# manuellsteuerung.net
KiCad netlist of a schematic drawn in EAGLE
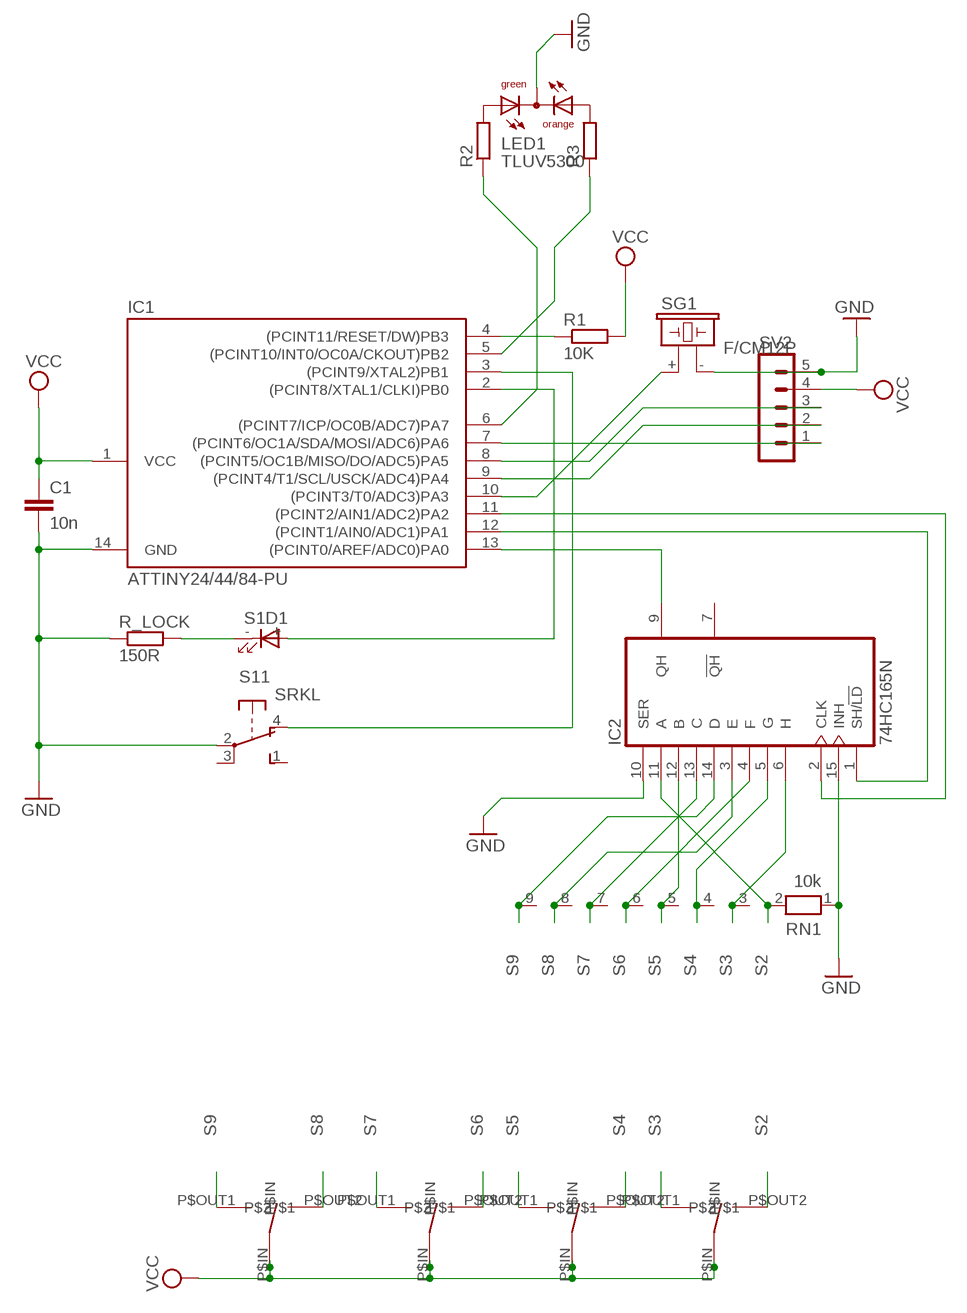
[diagram p0: schematic, sheet 1]

(export (version "E")
  (design (tool "Eeschema 10.0.6"))
  (components
    (comp (ref "C1")
      (value "10n")
      (footprint "eagle-import:C025-024X044")
      (libsource (lib "eagle-import") (part "C-EU025-024X044"))
    )
    (comp (ref "IC1")
      (value "ATTINY24/44/84-PU")
      (footprint "eagle-import:DIL14")
      (libsource (lib "eagle-import") (part "ATTINY24/44/84-PU"))
    )
    (comp (ref "IC2")
      (value "74HC165N")
      (footprint "eagle-import:DIL16")
      (libsource (lib "eagle-import") (part "74165NHC"))
    )
    (comp (ref "LED1")
      (value "TLUV5300")
      (footprint "eagle-import:TLUV5300")
      (libsource (lib "eagle-import") (part "TLUV5300"))
    )
    (comp (ref "R1")
      (value "10K")
      (footprint "eagle-import:0207_7")
      (libsource (lib "eagle-import") (part "R-EU_0207/7"))
    )
    (comp (ref "R2")
      (value "R-EU_0207/7")
      (footprint "eagle-import:0207_7")
      (libsource (lib "eagle-import") (part "R-EU_0207/7"))
    )
    (comp (ref "R3")
      (value "R-EU_0207/7")
      (footprint "eagle-import:0207_7")
      (libsource (lib "eagle-import") (part "R-EU_0207/7"))
    )
    (comp (ref "RN1")
      (value "10k")
      (footprint "eagle-import:RN-9")
      (libsource (lib "eagle-import") (part "RN08"))
    )
    (comp (ref "R_LOCK")
      (value "150R")
      (footprint "eagle-import:0207_10")
      (libsource (lib "eagle-import") (part "R-EU_0207/10"))
    )
    (comp (ref "S1")
      (value "SRKL")
      (footprint "eagle-import:SRKL")
      (libsource (lib "eagle-import") (part "SRKL"))
    )
    (comp (ref "SG1")
      (value "F/CM12P")
      (footprint "eagle-import:F_CM12P")
      (libsource (lib "eagle-import") (part "F/CM12P"))
    )
    (comp (ref "SV2")
      (value "MA05-1")
      (footprint "eagle-import:MA05-1")
      (libsource (lib "eagle-import") (part "MA05-1"))
    )
    (comp (ref "U$1")
      (value "MS_500E")
      (footprint "eagle-import:MS_500E")
      (libsource (lib "eagle-import") (part "MS_500E"))
    )
    (comp (ref "U$2")
      (value "MS_500E")
      (footprint "eagle-import:MS_500E")
      (libsource (lib "eagle-import") (part "MS_500E"))
    )
    (comp (ref "U$3")
      (value "MS_500E")
      (footprint "eagle-import:MS_500E")
      (libsource (lib "eagle-import") (part "MS_500E"))
    )
    (comp (ref "U$4")
      (value "MS_500E")
      (footprint "eagle-import:MS_500E")
      (libsource (lib "eagle-import") (part "MS_500E"))
    )
  )
  (nets
    (net (code "1") (name "/S2") (class "Default")
      (node (ref "IC2") (pin "11") (pinfunction "A_11") (pintype "input"))
      (node (ref "RN1") (pin "2") (pinfunction "2_2") (pintype "passive"))
      (node (ref "U$4") (pin "P$OUT2") (pinfunction "P$2_P$OUT2") (pintype "bidirectional"))
    )
    (net (code "2") (name "/S3") (class "Default")
      (node (ref "IC2") (pin "6") (pinfunction "H_6") (pintype "input"))
      (node (ref "RN1") (pin "3") (pinfunction "3_3") (pintype "passive"))
      (node (ref "U$4") (pin "P$OUT1") (pinfunction "P$1_P$OUT1") (pintype "bidirectional"))
    )
    (net (code "3") (name "/S4") (class "Default")
      (node (ref "IC2") (pin "5") (pinfunction "G_5") (pintype "input"))
      (node (ref "RN1") (pin "4") (pinfunction "4_4") (pintype "passive"))
      (node (ref "U$1") (pin "P$OUT2") (pinfunction "P$2_P$OUT2") (pintype "bidirectional"))
    )
    (net (code "4") (name "/S5") (class "Default")
      (node (ref "IC2") (pin "12") (pinfunction "B_12") (pintype "input"))
      (node (ref "RN1") (pin "5") (pinfunction "5_5") (pintype "passive"))
      (node (ref "U$1") (pin "P$OUT1") (pinfunction "P$1_P$OUT1") (pintype "bidirectional"))
    )
    (net (code "5") (name "/S6") (class "Default")
      (node (ref "IC2") (pin "4") (pinfunction "F_4") (pintype "input"))
      (node (ref "RN1") (pin "6") (pinfunction "6_6") (pintype "passive"))
      (node (ref "U$3") (pin "P$OUT2") (pinfunction "P$2_P$OUT2") (pintype "bidirectional"))
    )
    (net (code "6") (name "/S7") (class "Default")
      (node (ref "IC2") (pin "13") (pinfunction "C_13") (pintype "input"))
      (node (ref "RN1") (pin "7") (pinfunction "7_7") (pintype "passive"))
      (node (ref "U$3") (pin "P$OUT1") (pinfunction "P$1_P$OUT1") (pintype "bidirectional"))
    )
    (net (code "7") (name "/S8") (class "Default")
      (node (ref "IC2") (pin "3") (pinfunction "E_3") (pintype "input"))
      (node (ref "RN1") (pin "8") (pinfunction "8_8") (pintype "passive"))
      (node (ref "U$2") (pin "P$OUT2") (pinfunction "P$2_P$OUT2") (pintype "bidirectional"))
    )
    (net (code "8") (name "/S9") (class "Default")
      (node (ref "IC2") (pin "14") (pinfunction "D_14") (pintype "input"))
      (node (ref "RN1") (pin "9") (pinfunction "9_9") (pintype "passive"))
      (node (ref "U$2") (pin "P$OUT1") (pinfunction "P$1_P$OUT1") (pintype "bidirectional"))
    )
    (net (code "9") (name "GND") (class "Default")
      (node (ref "C1") (pin "2") (pinfunction "2_2") (pintype "passive"))
      (node (ref "IC1") (pin "14") (pinfunction "GND_14") (pintype "power_in"))
      (node (ref "IC2") (pin "10") (pinfunction "SER_10") (pintype "input"))
      (node (ref "IC2") (pin "15") (pinfunction "INH_15") (pintype "input"))
      (node (ref "LED1") (pin "CC") (pinfunction "CC_CC") (pintype "passive"))
      (node (ref "RN1") (pin "1") (pinfunction "1_1") (pintype "passive"))
      (node (ref "R_LOCK") (pin "1") (pinfunction "1_1") (pintype "passive"))
      (node (ref "S1") (pin "2") (pinfunction "P_2") (pintype "passive"))
      (node (ref "SG1") (pin "-") (pinfunction "2_-") (pintype "passive"))
      (node (ref "SV2") (pin "5") (pinfunction "5_5") (pintype "passive"))
    )
    (net (code "10") (name "Net-(IC1-(PCINT0{slash}AREF{slash}ADC0)PA0)") (class "Default")
      (node (ref "IC1") (pin "13") (pinfunction "(PCINT0/AREF/ADC0)PA0_13") (pintype "bidirectional"))
      (node (ref "IC2") (pin "9") (pinfunction "QH_9") (pintype "output"))
    )
    (net (code "11") (name "Net-(IC1-(PCINT1{slash}AIN0{slash}ADC1)PA1)") (class "Default")
      (node (ref "IC1") (pin "12") (pinfunction "(PCINT1/AIN0/ADC1)PA1_12") (pintype "bidirectional"))
      (node (ref "IC2") (pin "1") (pinfunction "SH/~{LD}_1") (pintype "input"))
    )
    (net (code "12") (name "Net-(IC1-(PCINT2{slash}AIN1{slash}ADC2)PA2)") (class "Default")
      (node (ref "IC1") (pin "11") (pinfunction "(PCINT2/AIN1/ADC2)PA2_11") (pintype "bidirectional"))
      (node (ref "IC2") (pin "2") (pinfunction "CLK_2") (pintype "input"))
    )
    (net (code "13") (name "Net-(IC1-(PCINT3{slash}T0{slash}ADC3)PA3)") (class "Default")
      (node (ref "IC1") (pin "10") (pinfunction "(PCINT3/T0/ADC3)PA3_10") (pintype "bidirectional"))
      (node (ref "SG1") (pin "+") (pinfunction "1_+") (pintype "passive"))
    )
    (net (code "14") (name "Net-(IC1-(PCINT4{slash}T1{slash}SCL{slash}USCK{slash}ADC4)PA4)") (class "Default")
      (node (ref "IC1") (pin "9") (pinfunction "(PCINT4/T1/SCL/USCK/ADC4)PA4_9") (pintype "bidirectional"))
      (node (ref "SV2") (pin "2") (pinfunction "2_2") (pintype "passive"))
    )
    (net (code "15") (name "Net-(IC1-(PCINT5{slash}OC1B{slash}MISO{slash}DO{slash}ADC5)PA5)") (class "Default")
      (node (ref "IC1") (pin "8") (pinfunction "(PCINT5/OC1B/MISO/DO/ADC5)PA5_8") (pintype "bidirectional"))
      (node (ref "SV2") (pin "3") (pinfunction "3_3") (pintype "passive"))
    )
    (net (code "16") (name "Net-(IC1-(PCINT6{slash}OC1A{slash}SDA{slash}MOSI{slash}ADC6)PA6)") (class "Default")
      (node (ref "IC1") (pin "7") (pinfunction "(PCINT6/OC1A/SDA/MOSI/ADC6)PA6_7") (pintype "bidirectional"))
      (node (ref "SV2") (pin "1") (pinfunction "1_1") (pintype "passive"))
    )
    (net (code "17") (name "Net-(IC1-(PCINT7{slash}ICP{slash}OC0B{slash}ADC7)PA7)") (class "Default")
      (node (ref "IC1") (pin "6") (pinfunction "(PCINT7/ICP/OC0B/ADC7)PA7_6") (pintype "bidirectional"))
      (node (ref "R2") (pin "1") (pinfunction "1_1") (pintype "passive"))
    )
    (net (code "18") (name "Net-(IC1-(PCINT8{slash}XTAL1{slash}CLKI)PB0)") (class "Default")
      (node (ref "IC1") (pin "2") (pinfunction "(PCINT8/XTAL1/CLKI)PB0_2") (pintype "bidirectional"))
      (node (ref "S1") (pin "+") (pinfunction "A_+") (pintype "passive"))
    )
    (net (code "19") (name "Net-(IC1-(PCINT9{slash}XTAL2)PB1)") (class "Default")
      (node (ref "IC1") (pin "3") (pinfunction "(PCINT9/XTAL2)PB1_3") (pintype "bidirectional"))
      (node (ref "S1") (pin "4") (pinfunction "O_4") (pintype "passive"))
    )
    (net (code "20") (name "Net-(IC1-(PCINT10{slash}INT0{slash}OC0A{slash}CKOUT)PB2)") (class "Default")
      (node (ref "IC1") (pin "5") (pinfunction "(PCINT10/INT0/OC0A/CKOUT)PB2_5") (pintype "bidirectional"))
      (node (ref "R3") (pin "1") (pinfunction "1_1") (pintype "passive"))
    )
    (net (code "21") (name "Net-(IC1-(PCINT11{slash}RESET{slash}DW)PB3)") (class "Default")
      (node (ref "IC1") (pin "4") (pinfunction "(PCINT11/RESET/DW)PB3_4") (pintype "bidirectional"))
      (node (ref "R1") (pin "1") (pinfunction "1_1") (pintype "passive"))
    )
    (net (code "22") (name "Net-(LED1-PadAG)") (class "Default")
      (node (ref "LED1") (pin "AG") (pinfunction "AG_AG") (pintype "passive"))
      (node (ref "R2") (pin "2") (pinfunction "2_2") (pintype "passive"))
    )
    (net (code "23") (name "Net-(LED1-PadAO)") (class "Default")
      (node (ref "LED1") (pin "AO") (pinfunction "AO_AO") (pintype "passive"))
      (node (ref "R3") (pin "2") (pinfunction "2_2") (pintype "passive"))
    )
    (net (code "24") (name "Net-(S1B-C)") (class "Default")
      (node (ref "R_LOCK") (pin "2") (pinfunction "2_2") (pintype "passive"))
      (node (ref "S1") (pin "-") (pinfunction "C_-") (pintype "passive"))
    )
    (net (code "25") (name "VCC") (class "Default")
      (node (ref "C1") (pin "1") (pinfunction "1_1") (pintype "passive"))
      (node (ref "IC1") (pin "1") (pinfunction "VCC_1") (pintype "power_in"))
      (node (ref "R1") (pin "2") (pinfunction "2_2") (pintype "passive"))
      (node (ref "SV2") (pin "4") (pinfunction "4_4") (pintype "passive"))
      (node (ref "U$1") (pin "P$IN") (pinfunction "P$IN_P$IN") (pintype "bidirectional"))
      (node (ref "U$2") (pin "P$IN") (pinfunction "P$IN_P$IN") (pintype "bidirectional"))
      (node (ref "U$3") (pin "P$IN") (pinfunction "P$IN_P$IN") (pintype "bidirectional"))
      (node (ref "U$4") (pin "P$IN") (pinfunction "P$IN_P$IN") (pintype "bidirectional"))
    )
    (net (code "26") (name "unconnected-(IC2A-~{QH}-Pad7)") (class "Default")
      (node (ref "IC2") (pin "7") (pinfunction "~{QH}_7") (pintype "output"))
    )
    (net (code "27") (name "unconnected-(S1A-P-Pad3)") (class "Default")
      (node (ref "S1") (pin "3") (pinfunction "P_3") (pintype "passive"))
    )
    (net (code "28") (name "unconnected-(S1A-S-Pad1)") (class "Default")
      (node (ref "S1") (pin "1") (pinfunction "S_1") (pintype "passive"))
    )
  )
)
